# design.net
KiCad netlist of a schematic drawn in Altium Designer
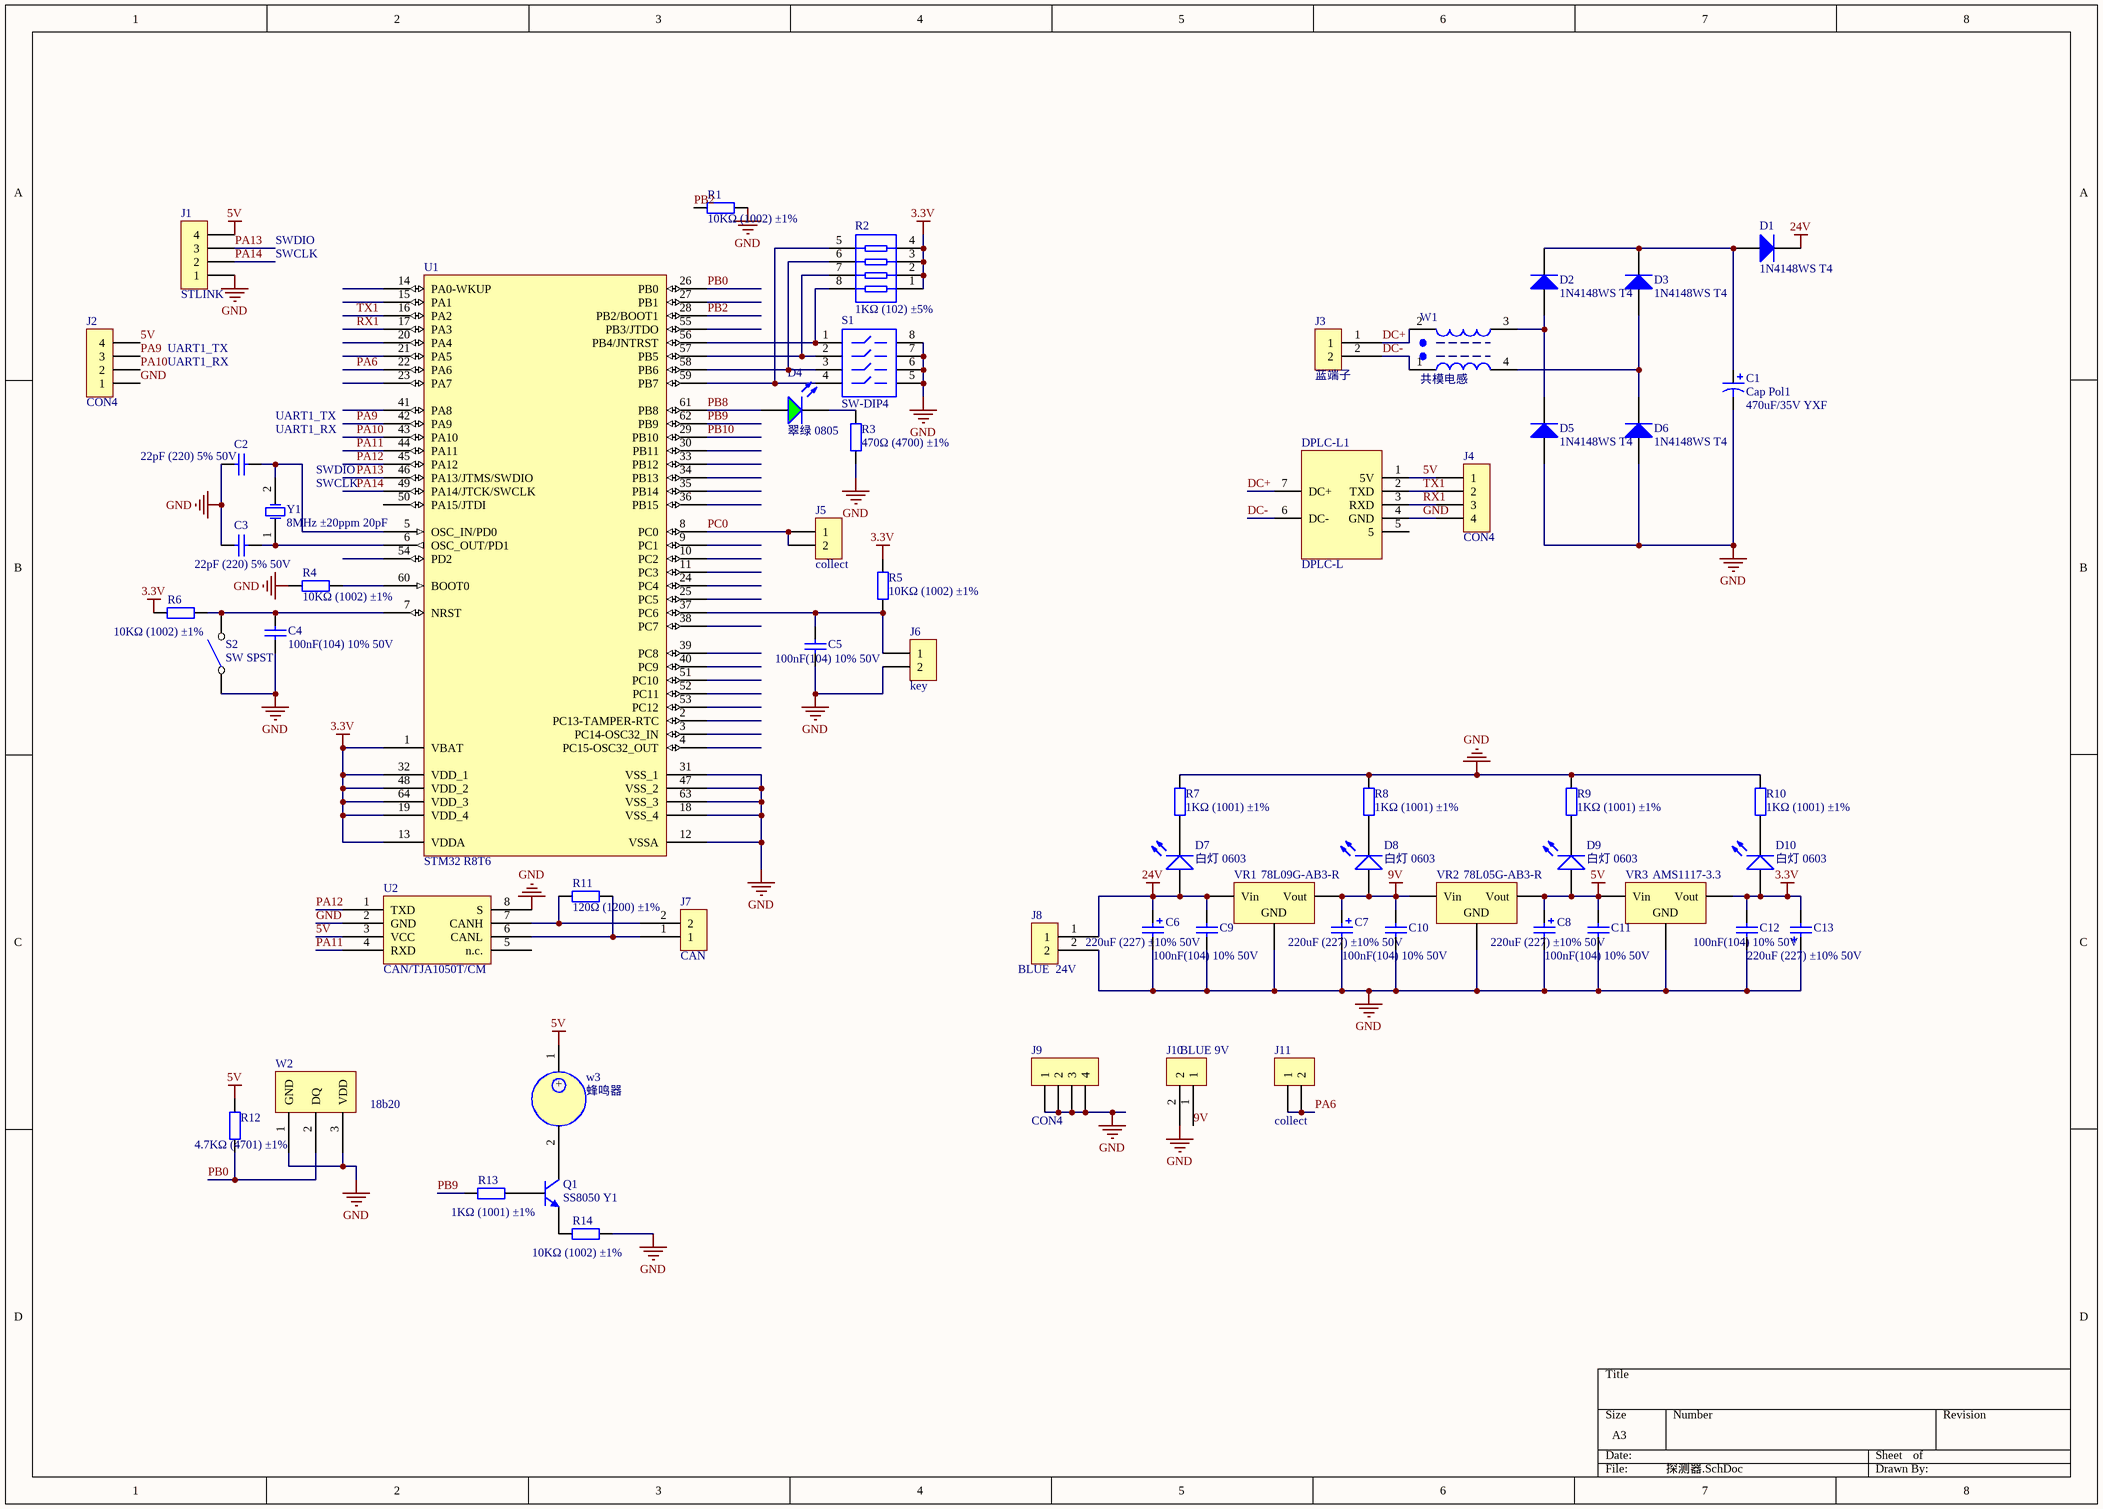
[diagram p0: 探测器.SchDoc]

(export (version "E")
  (design (tool "Eeschema 10.0.6"))
  (components
    (comp (ref "C1")
      (value "Cap Pol1")
      (footprint "RB.2/.4")
      (description "Polarized Capacitor (Radial)")
      (fields (field (name "ALTIUM_VALUE") "470uF/35V YXF") (field (name "PUBLISHER") "Altium Limited"))
      (libsource (lib "Miscellaneous Devices") (part "Cap Pol1"))
    )
    (comp (ref "C2")
      (value "22pF (220) 5% 50V")
      (footprint "LC-0805_C")
      (description "贴片电容")
      (libsource (lib "Miscellaneous Devices LC") (part "0805 22pF (220) 5% 50V"))
    )
    (comp (ref "C3")
      (value "22pF (220) 5% 50V")
      (footprint "LC-0805_C")
      (description "贴片电容")
      (libsource (lib "Miscellaneous Devices LC") (part "0805 22pF (220) 5% 50V"))
    )
    (comp (ref "C4")
      (value "100nF(104) 10% 50V")
      (footprint "LC-0805_C")
      (description "贴片电容")
      (libsource (lib "Miscellaneous Devices LC") (part "0805 100nF(104) 10% 50V"))
    )
    (comp (ref "C5")
      (value "100nF(104) 10% 50V")
      (footprint "LC-0805_C")
      (description "贴片电容")
      (libsource (lib "Miscellaneous Devices LC") (part "0805 100nF(104) 10% 50V"))
    )
    (comp (ref "C6")
      (value "220uF (227) ±10% 50V")
      (footprint "LC-CASE-B_3528")
      (description "钽电容")
      (libsource (lib "Miscellaneous Devices LC") (part "3528 100uF (107) 10% 6.3V"))
    )
    (comp (ref "C7")
      (value "220uF (227) ±10% 50V")
      (footprint "LC-CASE-B_3528")
      (description "钽电容")
      (libsource (lib "Miscellaneous Devices LC") (part "3528 100uF (107) 10% 6.3V"))
    )
    (comp (ref "C8")
      (value "220uF (227) ±10% 50V")
      (footprint "LC-CASE-B_3528")
      (description "钽电容")
      (libsource (lib "Miscellaneous Devices LC") (part "3528 100uF (107) 10% 6.3V"))
    )
    (comp (ref "C9")
      (value "100nF(104) 10% 50V")
      (footprint "LC-0805_C")
      (description "贴片电容")
      (libsource (lib "Miscellaneous Devices LC") (part "0805 100nF(104) 10% 50V"))
    )
    (comp (ref "C10")
      (value "100nF(104) 10% 50V")
      (footprint "LC-0805_C")
      (description "贴片电容")
      (libsource (lib "Miscellaneous Devices LC") (part "0805 100nF(104) 10% 50V"))
    )
    (comp (ref "C11")
      (value "100nF(104) 10% 50V")
      (footprint "LC-0805_C")
      (description "贴片电容")
      (libsource (lib "Miscellaneous Devices LC") (part "0805 100nF(104) 10% 50V"))
    )
    (comp (ref "C12")
      (value "100nF(104) 10% 50V")
      (footprint "LC-0805_C")
      (description "贴片电容")
      (libsource (lib "Miscellaneous Devices LC") (part "0805 100nF(104) 10% 50V"))
    )
    (comp (ref "C13")
      (value "220uF (227) ±10% 50V")
      (footprint "LC-CASE-B_3528")
      (description "钽电容")
      (libsource (lib "Miscellaneous Devices LC") (part "3528 100uF (107) 10% 6.3V"))
    )
    (comp (ref "D1")
      (value "1N4148WS T4")
      (footprint "LC-SOD-323")
      (description "二极管")
      (libsource (lib "Miscellaneous Devices LC") (part "SOD-323 1N4148WS T4"))
    )
    (comp (ref "D2")
      (value "1N4148WS T4")
      (footprint "LC-SOD-323")
      (description "二极管")
      (libsource (lib "Miscellaneous Devices LC") (part "SOD-323 1N4148WS T4"))
    )
    (comp (ref "D3")
      (value "1N4148WS T4")
      (footprint "LC-SOD-323")
      (description "二极管")
      (libsource (lib "Miscellaneous Devices LC") (part "SOD-323 1N4148WS T4"))
    )
    (comp (ref "D4")
      (value "翠绿 0805")
      (footprint "LC-0805_LED_S1")
      (description "发光二极管")
      (libsource (lib "Miscellaneous Devices LC") (part "0805 翠绿"))
    )
    (comp (ref "D5")
      (value "1N4148WS T4")
      (footprint "LC-SOD-323")
      (description "二极管")
      (libsource (lib "Miscellaneous Devices LC") (part "SOD-323 1N4148WS T4"))
    )
    (comp (ref "D6")
      (value "1N4148WS T4")
      (footprint "LC-SOD-323")
      (description "二极管")
      (libsource (lib "Miscellaneous Devices LC") (part "SOD-323 1N4148WS T4"))
    )
    (comp (ref "D7")
      (value "白灯 0603")
      (footprint "LC-0603_LED_S1")
      (description "发光二极管")
      (libsource (lib "Miscellaneous Devices LC") (part "0603 白灯"))
    )
    (comp (ref "D8")
      (value "白灯 0603")
      (footprint "LC-0603_LED_S1")
      (description "发光二极管")
      (libsource (lib "Miscellaneous Devices LC") (part "0603 白灯"))
    )
    (comp (ref "D9")
      (value "白灯 0603")
      (footprint "LC-0603_LED_S1")
      (description "发光二极管")
      (libsource (lib "Miscellaneous Devices LC") (part "0603 白灯"))
    )
    (comp (ref "D10")
      (value "白灯 0603")
      (footprint "LC-0603_LED_S1")
      (description "发光二极管")
      (libsource (lib "Miscellaneous Devices LC") (part "0603 白灯"))
    )
    (comp (ref "DPLC-L1") (value "DPLC-L") (footprint "DPLC-L") (libsource (lib "毕设原理图封装库") (part "DPLC-L")))
    (comp (ref "J1") (value "STLINK") (footprint "SIP4") (libsource (lib "") (part "CON4_1")))
    (comp (ref "J2") (value "CON4") (footprint "SIP4") (libsource (lib "") (part "CON4_1")))
    (comp (ref "J3") (value "蓝端子") (footprint "蓝端子") (libsource (lib "") (part "蓝端子_1")))
    (comp (ref "J4") (value "CON4") (footprint "SIP4") (libsource (lib "") (part "CON4_2")))
    (comp (ref "J5") (value "collect") (footprint "SIP2") (libsource (lib "毕设原理图封装库") (part "CON2")))
    (comp (ref "J6") (value "key") (footprint "SIP2") (libsource (lib "毕设原理图封装库") (part "CON2")))
    (comp (ref "J7") (value "CAN") (footprint "蓝端子") (libsource (lib "毕设原理图封装库") (part "蓝端子")))
    (comp (ref "J8") (value "BLUE  24V") (footprint "蓝端子") (libsource (lib "") (part "蓝端子_1")))
    (comp (ref "J9") (value "CON4") (footprint "SIP4") (libsource (lib "毕设原理图封装库") (part "CON4")))
    (comp (ref "J10") (value "BLUE 9V") (footprint "蓝端子") (libsource (lib "") (part "蓝端子_2")))
    (comp (ref "J11") (value "collect") (footprint "SIP2") (libsource (lib "") (part "CON2_1")))
    (comp (ref "Q1")
      (value "SS8050 Y1")
      (footprint "LC-SOT-23(SOT-23-3)")
      (description "三极管")
      (libsource (lib "Miscellaneous Devices LC") (part "SOT-23 SS8050 Y1"))
    )
    (comp (ref "R1")
      (value "10KΩ (1002) ±1%")
      (footprint "LC-0805_R")
      (description "贴片电阻")
      (libsource (lib "Miscellaneous Devices LC") (part "0805 10KΩ (1002) 1%"))
    )
    (comp (ref "R2")
      (value "1KΩ (102) ±5%")
      (footprint "LC-0603_Rx4")
      (description "贴片排阻")
      (libsource (lib "Miscellaneous Devices LC") (part "0603*4  1KΩ (102) 5%"))
    )
    (comp (ref "R3")
      (value "470Ω (4700) ±1%")
      (footprint "LC-0805_R")
      (description "贴片电阻")
      (libsource (lib "Miscellaneous Devices LC") (part "0805 470Ω (4700) 1%"))
    )
    (comp (ref "R4")
      (value "10KΩ (1002) ±1%")
      (footprint "LC-0805_R")
      (description "贴片电阻")
      (libsource (lib "") (part "0805 10KΩ (1002) 1%_2"))
    )
    (comp (ref "R5")
      (value "10KΩ (1002) ±1%")
      (footprint "LC-0805_R")
      (description "贴片电阻")
      (libsource (lib "") (part "0805 10KΩ (1002) 1%_1"))
    )
    (comp (ref "R6")
      (value "10KΩ (1002) ±1%")
      (footprint "LC-0805_R")
      (description "贴片电阻")
      (libsource (lib "") (part "0805 10KΩ (1002) 1%_2"))
    )
    (comp (ref "R7")
      (value "1KΩ (1001) ±1%")
      (footprint "LC-0603_R")
      (description "贴片电阻")
      (libsource (lib "Miscellaneous Devices LC") (part "0603 1KΩ (1001) 1%"))
    )
    (comp (ref "R8")
      (value "1KΩ (1001) ±1%")
      (footprint "LC-0603_R")
      (description "贴片电阻")
      (libsource (lib "Miscellaneous Devices LC") (part "0603 1KΩ (1001) 1%"))
    )
    (comp (ref "R9")
      (value "1KΩ (1001) ±1%")
      (footprint "LC-0603_R")
      (description "贴片电阻")
      (libsource (lib "Miscellaneous Devices LC") (part "0603 1KΩ (1001) 1%"))
    )
    (comp (ref "R10")
      (value "1KΩ (1001) ±1%")
      (footprint "LC-0603_R")
      (description "贴片电阻")
      (libsource (lib "Miscellaneous Devices LC") (part "0603 1KΩ (1001) 1%"))
    )
    (comp (ref "R11")
      (value "120Ω (1200) ±1%")
      (footprint "LC-0805_R")
      (description "贴片电阻")
      (libsource (lib "Miscellaneous Devices LC") (part "0805 120Ω (1200) 1%"))
    )
    (comp (ref "R12")
      (value "4.7KΩ (4701) ±1%")
      (footprint "LC-0805_R")
      (description "贴片电阻")
      (libsource (lib "Miscellaneous Devices LC") (part "0805 4.7KΩ (4701) 1%"))
    )
    (comp (ref "R13")
      (value "1KΩ (1001) ±1%")
      (footprint "LC-0805_R")
      (description "贴片电阻")
      (libsource (lib "Miscellaneous Devices LC") (part "0805 1KΩ (1001) 1%"))
    )
    (comp (ref "R14")
      (value "10KΩ (1002) ±1%")
      (footprint "LC-0805_R")
      (description "贴片电阻")
      (libsource (lib "") (part "0805 10KΩ (1002) 1%_2"))
    )
    (comp (ref "S1")
      (value "SW-DIP4")
      (footprint "4位拨码开关")
      (description "4位拨码开关")
      (libsource (lib "毕设原理图封装库") (part "SW-DIP4"))
    )
    (comp (ref "S2")
      (value "SW SPST")
      (footprint "单片机小按键")
      (description "单刀单掷开关")
      (libsource (lib "毕设原理图封装库") (part "SW SPST"))
    )
    (comp (ref "U1")
      (value "STM32 R8T6")
      (footprint "LC-LQFP-64_10x10x05P")
      (libsource (lib "毕设原理图封装库") (part "STM32 R8T6"))
    )
    (comp (ref "U2")
      (value "CAN/TJA1050T/CM")
      (footprint "LC-SOIC-8_150mil")
      (description "CAN")
      (libsource (lib "Miscellaneous Devices LC") (part "CAN/TJA1050T/CM"))
    )
    (comp (ref "VR1")
      (value "78L09G-AB3-R")
      (footprint "LC-SOT-89(SOT-89-3)")
      (description "低压差线性稳压(LDO)")
      (libsource (lib "Miscellaneous Devices LC") (part "SOT-89 78L12G-AB3-R"))
    )
    (comp (ref "VR2")
      (value "78L05G-AB3-R")
      (footprint "LC-SOT-89(SOT-89-3)")
      (description "低压差线性稳压(LDO)")
      (libsource (lib "Miscellaneous Devices LC") (part "SOT-89 78L05G-AB3-R"))
    )
    (comp (ref "VR3")
      (value "AMS1117-3.3")
      (footprint "LC-SOT-223")
      (description "低压差线性稳压(LDO)")
      (libsource (lib "Miscellaneous Devices LC") (part "SOT-223 AMS1117-3.3"))
    )
    (comp (ref "W1") (value "共模电感") (footprint "共模电感") (libsource (lib "毕设原理图封装库") (part "共模电感")))
    (comp (ref "W2") (value "18b20") (footprint "DS18B20") (libsource (lib "毕设原理图封装库") (part "18b20")))
    (comp (ref "w3") (value "蜂鸣器") (footprint "蜂鸣器") (libsource (lib "毕设原理图封装库") (part "蜂鸣器")))
    (comp (ref "Y1")
      (value "8MHz ±20ppm 20pF")
      (footprint "LC-SMD-5032_2P")
      (description "贴片晶振")
      (libsource (lib "Miscellaneous Devices LC") (part "SMD-5032_2P 8MHz 20ppm 20pF"))
    )
  )
  (nets
    (net (code "1") (name "/DC+") (class "Default")
      (node (ref "DPLC-L1") (pin "7") (pinfunction "DC+_7") (pintype "passive"))
      (node (ref "J3") (pin "1") (pinfunction "1_1") (pintype "passive"))
      (node (ref "W1") (pin "2") (pinfunction "2_2") (pintype "passive"))
    )
    (net (code "2") (name "/DC-") (class "Default")
      (node (ref "DPLC-L1") (pin "6") (pinfunction "DC-_6") (pintype "passive"))
      (node (ref "J3") (pin "2") (pinfunction "2_2") (pintype "passive"))
      (node (ref "W1") (pin "1") (pinfunction "1_1") (pintype "passive"))
    )
    (net (code "3") (name "/PA6") (class "Default")
      (node (ref "J11") (pin "1") (pinfunction "1_1") (pintype "passive"))
      (node (ref "J11") (pin "2") (pinfunction "2_2") (pintype "passive"))
      (node (ref "U1") (pin "22") (pinfunction "PA6_22") (pintype "bidirectional"))
    )
    (net (code "4") (name "/PA9") (class "Default")
      (node (ref "J2") (pin "3") (pinfunction "3_3") (pintype "passive"))
      (node (ref "U1") (pin "42") (pinfunction "PA9_42") (pintype "bidirectional"))
    )
    (net (code "5") (name "/PA10") (class "Default")
      (node (ref "J2") (pin "2") (pinfunction "2_2") (pintype "passive"))
      (node (ref "U1") (pin "43") (pinfunction "PA10_43") (pintype "bidirectional"))
    )
    (net (code "6") (name "/PA11") (class "Default")
      (node (ref "U1") (pin "44") (pinfunction "PA11_44") (pintype "bidirectional"))
      (node (ref "U2") (pin "4") (pinfunction "RXD_4") (pintype "passive"))
    )
    (net (code "7") (name "/PA12") (class "Default")
      (node (ref "U1") (pin "45") (pinfunction "PA12_45") (pintype "bidirectional"))
      (node (ref "U2") (pin "1") (pinfunction "TXD_1") (pintype "passive"))
    )
    (net (code "8") (name "/PA13") (class "Default")
      (node (ref "J1") (pin "3") (pinfunction "3_3") (pintype "passive"))
      (node (ref "U1") (pin "46") (pinfunction "PA13/JTMS/SWDIO_46") (pintype "bidirectional"))
    )
    (net (code "9") (name "/PA14") (class "Default")
      (node (ref "J1") (pin "2") (pinfunction "2_2") (pintype "passive"))
      (node (ref "U1") (pin "49") (pinfunction "PA14/JTCK/SWCLK_49") (pintype "bidirectional"))
    )
    (net (code "10") (name "/PB0") (class "Default")
      (node (ref "R12") (pin "1") (pinfunction "1_1") (pintype "passive"))
      (node (ref "U1") (pin "26") (pinfunction "PB0_26") (pintype "bidirectional"))
      (node (ref "W2") (pin "2") (pinfunction "DQ_2") (pintype "passive"))
    )
    (net (code "11") (name "/PB2") (class "Default")
      (node (ref "R1") (pin "2") (pinfunction "2_2") (pintype "passive"))
      (node (ref "U1") (pin "28") (pinfunction "PB2/BOOT1_28") (pintype "bidirectional"))
    )
    (net (code "12") (name "/PB8") (class "Default")
      (node (ref "D4") (pin "A") (pinfunction "A_A") (pintype "passive"))
      (node (ref "U1") (pin "61") (pinfunction "PB8_61") (pintype "bidirectional"))
    )
    (net (code "13") (name "/PB9") (class "Default")
      (node (ref "R13") (pin "1") (pinfunction "1_1") (pintype "passive"))
      (node (ref "U1") (pin "62") (pinfunction "PB9_62") (pintype "bidirectional"))
    )
    (net (code "14") (name "/PB10") (class "Default")
      (node (ref "U1") (pin "29") (pinfunction "PB10_29") (pintype "bidirectional"))
    )
    (net (code "15") (name "/PC0") (class "Default")
      (node (ref "J5") (pin "1") (pinfunction "1_1") (pintype "passive"))
      (node (ref "J5") (pin "2") (pinfunction "2_2") (pintype "passive"))
      (node (ref "U1") (pin "8") (pinfunction "PC0_8") (pintype "bidirectional"))
    )
    (net (code "16") (name "/RX1") (class "Default")
      (node (ref "DPLC-L1") (pin "3") (pinfunction "RXD_3") (pintype "passive"))
      (node (ref "J4") (pin "3") (pinfunction "3_3") (pintype "passive"))
      (node (ref "U1") (pin "17") (pinfunction "PA3_17") (pintype "bidirectional"))
    )
    (net (code "17") (name "/TX1") (class "Default")
      (node (ref "DPLC-L1") (pin "2") (pinfunction "TXD_2") (pintype "passive"))
      (node (ref "J4") (pin "2") (pinfunction "2_2") (pintype "passive"))
      (node (ref "U1") (pin "16") (pinfunction "PA2_16") (pintype "bidirectional"))
    )
    (net (code "18") (name "3.3V") (class "Default")
      (node (ref "C12") (pin "1") (pinfunction "1_1") (pintype "passive"))
      (node (ref "C13") (pin "2") (pinfunction "2_2") (pintype "passive"))
      (node (ref "D10") (pin "A") (pinfunction "A_A") (pintype "passive"))
      (node (ref "R2") (pin "1") (pinfunction "1_1") (pintype "passive"))
      (node (ref "R2") (pin "2") (pinfunction "2_2") (pintype "passive"))
      (node (ref "R2") (pin "3") (pinfunction "3_3") (pintype "passive"))
      (node (ref "R2") (pin "4") (pinfunction "4_4") (pintype "passive"))
      (node (ref "R5") (pin "2") (pinfunction "2_2") (pintype "passive"))
      (node (ref "R6") (pin "1") (pinfunction "1_1") (pintype "passive"))
      (node (ref "U1") (pin "1") (pinfunction "VBAT_1") (pintype "power_in"))
      (node (ref "U1") (pin "13") (pinfunction "VDDA_13") (pintype "power_in"))
      (node (ref "U1") (pin "19") (pinfunction "VDD_4_19") (pintype "power_in"))
      (node (ref "U1") (pin "32") (pinfunction "VDD_1_32") (pintype "power_in"))
      (node (ref "U1") (pin "48") (pinfunction "VDD_2_48") (pintype "power_in"))
      (node (ref "U1") (pin "64") (pinfunction "VDD_3_64") (pintype "power_in"))
      (node (ref "VR3") (pin "2") (pinfunction "Vout_2") (pintype "passive"))
    )
    (net (code "19") (name "5V") (class "Default")
      (node (ref "C11") (pin "2") (pinfunction "2_2") (pintype "passive"))
      (node (ref "C8") (pin "1") (pinfunction "1_1") (pintype "passive"))
      (node (ref "D9") (pin "A") (pinfunction "A_A") (pintype "passive"))
      (node (ref "DPLC-L1") (pin "1") (pinfunction "5V_1") (pintype "passive"))
      (node (ref "J1") (pin "4") (pinfunction "4_4") (pintype "passive"))
      (node (ref "J2") (pin "4") (pinfunction "4_4") (pintype "passive"))
      (node (ref "J4") (pin "1") (pinfunction "1_1") (pintype "passive"))
      (node (ref "R12") (pin "2") (pinfunction "2_2") (pintype "passive"))
      (node (ref "U2") (pin "3") (pinfunction "VCC_3") (pintype "passive"))
      (node (ref "VR2") (pin "3") (pinfunction "Vout_3") (pintype "passive"))
      (node (ref "VR3") (pin "3") (pinfunction "Vin_3") (pintype "passive"))
      (node (ref "w3") (pin "1") (pinfunction "+_1") (pintype "passive"))
    )
    (net (code "20") (name "9V") (class "Default")
      (node (ref "C10") (pin "2") (pinfunction "2_2") (pintype "passive"))
      (node (ref "C7") (pin "1") (pinfunction "1_1") (pintype "passive"))
      (node (ref "D8") (pin "A") (pinfunction "A_A") (pintype "passive"))
      (node (ref "J10") (pin "1") (pinfunction "1_1") (pintype "passive"))
      (node (ref "VR1") (pin "3") (pinfunction "Vout_3") (pintype "passive"))
      (node (ref "VR2") (pin "1") (pinfunction "Vin_1") (pintype "passive"))
    )
    (net (code "21") (name "24V") (class "Default")
      (node (ref "C6") (pin "1") (pinfunction "1_1") (pintype "passive"))
      (node (ref "C9") (pin "2") (pinfunction "2_2") (pintype "passive"))
      (node (ref "D1") (pin "2") (pinfunction "K_2") (pintype "passive"))
      (node (ref "D7") (pin "A") (pinfunction "A_A") (pintype "passive"))
      (node (ref "J8") (pin "1") (pinfunction "1_1") (pintype "passive"))
      (node (ref "VR1") (pin "1") (pinfunction "Vin_1") (pintype "passive"))
    )
    (net (code "22") (name "GND") (class "Default")
      (node (ref "C1") (pin "2") (pinfunction "2_2") (pintype "passive"))
      (node (ref "C10") (pin "1") (pinfunction "1_1") (pintype "passive"))
      (node (ref "C11") (pin "1") (pinfunction "1_1") (pintype "passive"))
      (node (ref "C12") (pin "2") (pinfunction "2_2") (pintype "passive"))
      (node (ref "C13") (pin "1") (pinfunction "1_1") (pintype "passive"))
      (node (ref "C2") (pin "1") (pinfunction "1_1") (pintype "passive"))
      (node (ref "C3") (pin "1") (pinfunction "1_1") (pintype "passive"))
      (node (ref "C4") (pin "1") (pinfunction "1_1") (pintype "passive"))
      (node (ref "C5") (pin "1") (pinfunction "1_1") (pintype "passive"))
      (node (ref "C6") (pin "2") (pinfunction "2_2") (pintype "passive"))
      (node (ref "C7") (pin "2") (pinfunction "2_2") (pintype "passive"))
      (node (ref "C8") (pin "2") (pinfunction "2_2") (pintype "passive"))
      (node (ref "C9") (pin "1") (pinfunction "1_1") (pintype "passive"))
      (node (ref "D5") (pin "1") (pinfunction "A_1") (pintype "passive"))
      (node (ref "D6") (pin "1") (pinfunction "A_1") (pintype "passive"))
      (node (ref "DPLC-L1") (pin "4") (pinfunction "GND_4") (pintype "passive"))
      (node (ref "J1") (pin "1") (pinfunction "1_1") (pintype "passive"))
      (node (ref "J10") (pin "2") (pinfunction "2_2") (pintype "passive"))
      (node (ref "J2") (pin "1") (pinfunction "1_1") (pintype "passive"))
      (node (ref "J4") (pin "4") (pinfunction "4_4") (pintype "passive"))
      (node (ref "J6") (pin "2") (pinfunction "2_2") (pintype "passive"))
      (node (ref "J8") (pin "2") (pinfunction "2_2") (pintype "passive"))
      (node (ref "J9") (pin "1") (pinfunction "1_1") (pintype "passive"))
      (node (ref "J9") (pin "2") (pinfunction "2_2") (pintype "passive"))
      (node (ref "J9") (pin "3") (pinfunction "3_3") (pintype "passive"))
      (node (ref "J9") (pin "4") (pinfunction "4_4") (pintype "passive"))
      (node (ref "R1") (pin "1") (pinfunction "1_1") (pintype "passive"))
      (node (ref "R10") (pin "1") (pinfunction "1_1") (pintype "passive"))
      (node (ref "R14") (pin "2") (pinfunction "2_2") (pintype "passive"))
      (node (ref "R3") (pin "1") (pinfunction "1_1") (pintype "passive"))
      (node (ref "R4") (pin "1") (pinfunction "1_1") (pintype "passive"))
      (node (ref "R7") (pin "1") (pinfunction "1_1") (pintype "passive"))
      (node (ref "R8") (pin "1") (pinfunction "1_1") (pintype "passive"))
      (node (ref "R9") (pin "1") (pinfunction "1_1") (pintype "passive"))
      (node (ref "S1") (pin "5") (pinfunction "5_5") (pintype "passive"))
      (node (ref "S1") (pin "6") (pinfunction "6_6") (pintype "passive"))
      (node (ref "S1") (pin "7") (pinfunction "7_7") (pintype "passive"))
      (node (ref "S1") (pin "8") (pinfunction "8_8") (pintype "passive"))
      (node (ref "S2") (pin "1") (pinfunction "COMMON_1") (pintype "passive"))
      (node (ref "U1") (pin "12") (pinfunction "VSSA_12") (pintype "power_in"))
      (node (ref "U1") (pin "18") (pinfunction "VSS_4_18") (pintype "power_in"))
      (node (ref "U1") (pin "31") (pinfunction "VSS_1_31") (pintype "power_in"))
      (node (ref "U1") (pin "47") (pinfunction "VSS_2_47") (pintype "power_in"))
      (node (ref "U1") (pin "63") (pinfunction "VSS_3_63") (pintype "power_in"))
      (node (ref "U2") (pin "2") (pinfunction "GND_2") (pintype "passive"))
      (node (ref "U2") (pin "8") (pinfunction "S_8") (pintype "passive"))
      (node (ref "VR1") (pin "2") (pinfunction "GND_2") (pintype "passive"))
      (node (ref "VR2") (pin "2") (pinfunction "GND_2") (pintype "passive"))
      (node (ref "VR3") (pin "1") (pinfunction "GND_1") (pintype "passive"))
      (node (ref "W2") (pin "1") (pinfunction "GND_1") (pintype "passive"))
      (node (ref "W2") (pin "3") (pinfunction "VDD_3") (pintype "passive"))
    )
    (net (code "23") (name "Net-(D1-A)") (class "Default")
      (node (ref "C1") (pin "1") (pinfunction "1_1") (pintype "passive"))
      (node (ref "D1") (pin "1") (pinfunction "A_1") (pintype "passive"))
      (node (ref "D2") (pin "2") (pinfunction "K_2") (pintype "passive"))
      (node (ref "D3") (pin "2") (pinfunction "K_2") (pintype "passive"))
    )
    (net (code "24") (name "Net-(D2-A)") (class "Default")
      (node (ref "D2") (pin "1") (pinfunction "A_1") (pintype "passive"))
      (node (ref "D5") (pin "2") (pinfunction "K_2") (pintype "passive"))
      (node (ref "W1") (pin "3") (pinfunction "3_3") (pintype "passive"))
    )
    (net (code "25") (name "Net-(D3-A)") (class "Default")
      (node (ref "D3") (pin "1") (pinfunction "A_1") (pintype "passive"))
      (node (ref "D6") (pin "2") (pinfunction "K_2") (pintype "passive"))
      (node (ref "W1") (pin "4") (pinfunction "4_4") (pintype "passive"))
    )
    (net (code "26") (name "Net-(D4-PadK)") (class "Default")
      (node (ref "D4") (pin "K") (pinfunction "K_K") (pintype "passive"))
      (node (ref "R3") (pin "2") (pinfunction "2_2") (pintype "passive"))
    )
    (net (code "27") (name "Net-(D7-PadK)") (class "Default")
      (node (ref "D7") (pin "K") (pinfunction "K_K") (pintype "passive"))
      (node (ref "R7") (pin "2") (pinfunction "2_2") (pintype "passive"))
    )
    (net (code "28") (name "Net-(D8-PadK)") (class "Default")
      (node (ref "D8") (pin "K") (pinfunction "K_K") (pintype "passive"))
      (node (ref "R8") (pin "2") (pinfunction "2_2") (pintype "passive"))
    )
    (net (code "29") (name "Net-(D9-PadK)") (class "Default")
      (node (ref "D9") (pin "K") (pinfunction "K_K") (pintype "passive"))
      (node (ref "R9") (pin "2") (pinfunction "2_2") (pintype "passive"))
    )
    (net (code "30") (name "Net-(D10-PadK)") (class "Default")
      (node (ref "D10") (pin "K") (pinfunction "K_K") (pintype "passive"))
      (node (ref "R10") (pin "2") (pinfunction "2_2") (pintype "passive"))
    )
    (net (code "31") (name "Net-(Q1-B)") (class "Default")
      (node (ref "Q1") (pin "1") (pinfunction "B_1") (pintype "passive"))
      (node (ref "R13") (pin "2") (pinfunction "2_2") (pintype "passive"))
    )
    (net (code "32") (name "Net-(Q1-C)") (class "Default")
      (node (ref "Q1") (pin "3") (pinfunction "C_3") (pintype "passive"))
      (node (ref "w3") (pin "2") (pintype "passive"))
    )
    (net (code "33") (name "Net-(Q1-E)") (class "Default")
      (node (ref "Q1") (pin "2") (pinfunction "E_2") (pintype "passive"))
      (node (ref "R14") (pin "1") (pinfunction "1_1") (pintype "passive"))
    )
    (net (code "34") (name "Net-(S2-NO)") (class "Default")
      (node (ref "C4") (pin "2") (pinfunction "2_2") (pintype "passive"))
      (node (ref "R6") (pin "2") (pinfunction "2_2") (pintype "passive"))
      (node (ref "S2") (pin "2") (pinfunction "NO_2") (pintype "passive"))
      (node (ref "U1") (pin "7") (pinfunction "NRST_7") (pintype "bidirectional"))
    )
    (net (code "35") (name "Net-(U1-BOOT0)") (class "Default")
      (node (ref "R4") (pin "2") (pinfunction "2_2") (pintype "passive"))
      (node (ref "U1") (pin "60") (pinfunction "BOOT0_60") (pintype "input"))
    )
    (net (code "36") (name "Net-(U1-OSC_IN{slash}PD0)") (class "Default")
      (node (ref "C2") (pin "2") (pinfunction "2_2") (pintype "passive"))
      (node (ref "U1") (pin "5") (pinfunction "OSC_IN/PD0_5") (pintype "input"))
      (node (ref "Y1") (pin "2") (pinfunction "OSC2_2") (pintype "passive"))
    )
    (net (code "37") (name "Net-(U1-OSC_OUT{slash}PD1)") (class "Default")
      (node (ref "C3") (pin "2") (pinfunction "2_2") (pintype "passive"))
      (node (ref "U1") (pin "6") (pinfunction "OSC_OUT/PD1_6") (pintype "output"))
      (node (ref "Y1") (pin "1") (pinfunction "OSC1_1") (pintype "passive"))
    )
    (net (code "38") (name "Net-(U1-PB4{slash}JNTRST)") (class "Default")
      (node (ref "R2") (pin "8") (pinfunction "8_8") (pintype "passive"))
      (node (ref "S1") (pin "1") (pinfunction "1_1") (pintype "passive"))
      (node (ref "U1") (pin "56") (pinfunction "PB4/JNTRST_56") (pintype "bidirectional"))
    )
    (net (code "39") (name "Net-(U1-PB5)") (class "Default")
      (node (ref "R2") (pin "7") (pinfunction "7_7") (pintype "passive"))
      (node (ref "S1") (pin "2") (pinfunction "2_2") (pintype "passive"))
      (node (ref "U1") (pin "57") (pinfunction "PB5_57") (pintype "bidirectional"))
    )
    (net (code "40") (name "Net-(U1-PB6)") (class "Default")
      (node (ref "R2") (pin "6") (pinfunction "6_6") (pintype "passive"))
      (node (ref "S1") (pin "3") (pinfunction "3_3") (pintype "passive"))
      (node (ref "U1") (pin "58") (pinfunction "PB6_58") (pintype "bidirectional"))
    )
    (net (code "41") (name "Net-(U1-PB7)") (class "Default")
      (node (ref "R2") (pin "5") (pinfunction "5_5") (pintype "passive"))
      (node (ref "S1") (pin "4") (pinfunction "4_4") (pintype "passive"))
      (node (ref "U1") (pin "59") (pinfunction "PB7_59") (pintype "bidirectional"))
    )
    (net (code "42") (name "Net-(U1-PC6)") (class "Default")
      (node (ref "C5") (pin "2") (pinfunction "2_2") (pintype "passive"))
      (node (ref "J6") (pin "1") (pinfunction "1_1") (pintype "passive"))
      (node (ref "R5") (pin "1") (pinfunction "1_1") (pintype "passive"))
      (node (ref "U1") (pin "37") (pinfunction "PC6_37") (pintype "bidirectional"))
    )
    (net (code "43") (name "Net-(U2-CANH)") (class "Default")
      (node (ref "J7") (pin "2") (pinfunction "2_2") (pintype "passive"))
      (node (ref "R11") (pin "1") (pinfunction "1_1") (pintype "passive"))
      (node (ref "U2") (pin "7") (pinfunction "CANH_7") (pintype "passive"))
    )
    (net (code "44") (name "Net-(U2-CANL)") (class "Default")
      (node (ref "J7") (pin "1") (pinfunction "1_1") (pintype "passive"))
      (node (ref "R11") (pin "2") (pinfunction "2_2") (pintype "passive"))
      (node (ref "U2") (pin "6") (pinfunction "CANL_6") (pintype "passive"))
    )
    (net (code "45") (name "unconnected-(DPLC-L1-Pad5)") (class "Default")
      (node (ref "DPLC-L1") (pin "5") (pinfunction "5_5") (pintype "passive"))
    )
    (net (code "46") (name "unconnected-(U1-PA0-WKUP-Pad14)") (class "Default")
      (node (ref "U1") (pin "14") (pinfunction "PA0-WKUP_14") (pintype "bidirectional"))
    )
    (net (code "47") (name "unconnected-(U1-PA1-Pad15)") (class "Default")
      (node (ref "U1") (pin "15") (pinfunction "PA1_15") (pintype "bidirectional"))
    )
    (net (code "48") (name "unconnected-(U1-PA4-Pad20)") (class "Default")
      (node (ref "U1") (pin "20") (pinfunction "PA4_20") (pintype "bidirectional"))
    )
    (net (code "49") (name "unconnected-(U1-PA5-Pad21)") (class "Default")
      (node (ref "U1") (pin "21") (pinfunction "PA5_21") (pintype "bidirectional"))
    )
    (net (code "50") (name "unconnected-(U1-PA7-Pad23)") (class "Default")
      (node (ref "U1") (pin "23") (pinfunction "PA7_23") (pintype "bidirectional"))
    )
    (net (code "51") (name "unconnected-(U1-PA8-Pad41)") (class "Default")
      (node (ref "U1") (pin "41") (pinfunction "PA8_41") (pintype "bidirectional"))
    )
    (net (code "52") (name "unconnected-(U1-PA15{slash}JTDI-Pad50)") (class "Default")
      (node (ref "U1") (pin "50") (pinfunction "PA15/JTDI_50") (pintype "bidirectional"))
    )
    (net (code "53") (name "unconnected-(U1-PB1-Pad27)") (class "Default")
      (node (ref "U1") (pin "27") (pinfunction "PB1_27") (pintype "bidirectional"))
    )
    (net (code "54") (name "unconnected-(U1-PB3{slash}JTDO-Pad55)") (class "Default")
      (node (ref "U1") (pin "55") (pinfunction "PB3/JTDO_55") (pintype "bidirectional"))
    )
    (net (code "55") (name "unconnected-(U1-PB11-Pad30)") (class "Default")
      (node (ref "U1") (pin "30") (pinfunction "PB11_30") (pintype "bidirectional"))
    )
    (net (code "56") (name "unconnected-(U1-PB12-Pad33)") (class "Default")
      (node (ref "U1") (pin "33") (pinfunction "PB12_33") (pintype "bidirectional"))
    )
    (net (code "57") (name "unconnected-(U1-PB13-Pad34)") (class "Default")
      (node (ref "U1") (pin "34") (pinfunction "PB13_34") (pintype "bidirectional"))
    )
    (net (code "58") (name "unconnected-(U1-PB14-Pad35)") (class "Default")
      (node (ref "U1") (pin "35") (pinfunction "PB14_35") (pintype "bidirectional"))
    )
    (net (code "59") (name "unconnected-(U1-PB15-Pad36)") (class "Default")
      (node (ref "U1") (pin "36") (pinfunction "PB15_36") (pintype "bidirectional"))
    )
    (net (code "60") (name "unconnected-(U1-PC1-Pad9)") (class "Default")
      (node (ref "U1") (pin "9") (pinfunction "PC1_9") (pintype "bidirectional"))
    )
    (net (code "61") (name "unconnected-(U1-PC2-Pad10)") (class "Default")
      (node (ref "U1") (pin "10") (pinfunction "PC2_10") (pintype "bidirectional"))
    )
    (net (code "62") (name "unconnected-(U1-PC3-Pad11)") (class "Default")
      (node (ref "U1") (pin "11") (pinfunction "PC3_11") (pintype "bidirectional"))
    )
    (net (code "63") (name "unconnected-(U1-PC4-Pad24)") (class "Default")
      (node (ref "U1") (pin "24") (pinfunction "PC4_24") (pintype "bidirectional"))
    )
    (net (code "64") (name "unconnected-(U1-PC5-Pad25)") (class "Default")
      (node (ref "U1") (pin "25") (pinfunction "PC5_25") (pintype "bidirectional"))
    )
    (net (code "65") (name "unconnected-(U1-PC7-Pad38)") (class "Default")
      (node (ref "U1") (pin "38") (pinfunction "PC7_38") (pintype "bidirectional"))
    )
    (net (code "66") (name "unconnected-(U1-PC8-Pad39)") (class "Default")
      (node (ref "U1") (pin "39") (pinfunction "PC8_39") (pintype "bidirectional"))
    )
    (net (code "67") (name "unconnected-(U1-PC9-Pad40)") (class "Default")
      (node (ref "U1") (pin "40") (pinfunction "PC9_40") (pintype "bidirectional"))
    )
    (net (code "68") (name "unconnected-(U1-PC10-Pad51)") (class "Default")
      (node (ref "U1") (pin "51") (pinfunction "PC10_51") (pintype "bidirectional"))
    )
    (net (code "69") (name "unconnected-(U1-PC11-Pad52)") (class "Default")
      (node (ref "U1") (pin "52") (pinfunction "PC11_52") (pintype "bidirectional"))
    )
    (net (code "70") (name "unconnected-(U1-PC12-Pad53)") (class "Default")
      (node (ref "U1") (pin "53") (pinfunction "PC12_53") (pintype "bidirectional"))
    )
    (net (code "71") (name "unconnected-(U1-PC13-TAMPER-RTC-Pad2)") (class "Default")
      (node (ref "U1") (pin "2") (pinfunction "PC13-TAMPER-RTC_2") (pintype "bidirectional"))
    )
    (net (code "72") (name "unconnected-(U1-PC14-OSC32_IN-Pad3)") (class "Default")
      (node (ref "U1") (pin "3") (pinfunction "PC14-OSC32_IN_3") (pintype "bidirectional"))
    )
    (net (code "73") (name "unconnected-(U1-PC15-OSC32_OUT-Pad4)") (class "Default")
      (node (ref "U1") (pin "4") (pinfunction "PC15-OSC32_OUT_4") (pintype "bidirectional"))
    )
    (net (code "74") (name "unconnected-(U1-PD2-Pad54)") (class "Default")
      (node (ref "U1") (pin "54") (pinfunction "PD2_54") (pintype "bidirectional"))
    )
    (net (code "75") (name "unconnected-(U2-n.c.-Pad5)") (class "Default")
      (node (ref "U2") (pin "5") (pinfunction "n.c._5") (pintype "passive"))
    )
  )
)
